# SupergunBasic.net
KiCad netlist of a schematic drawn in EAGLE
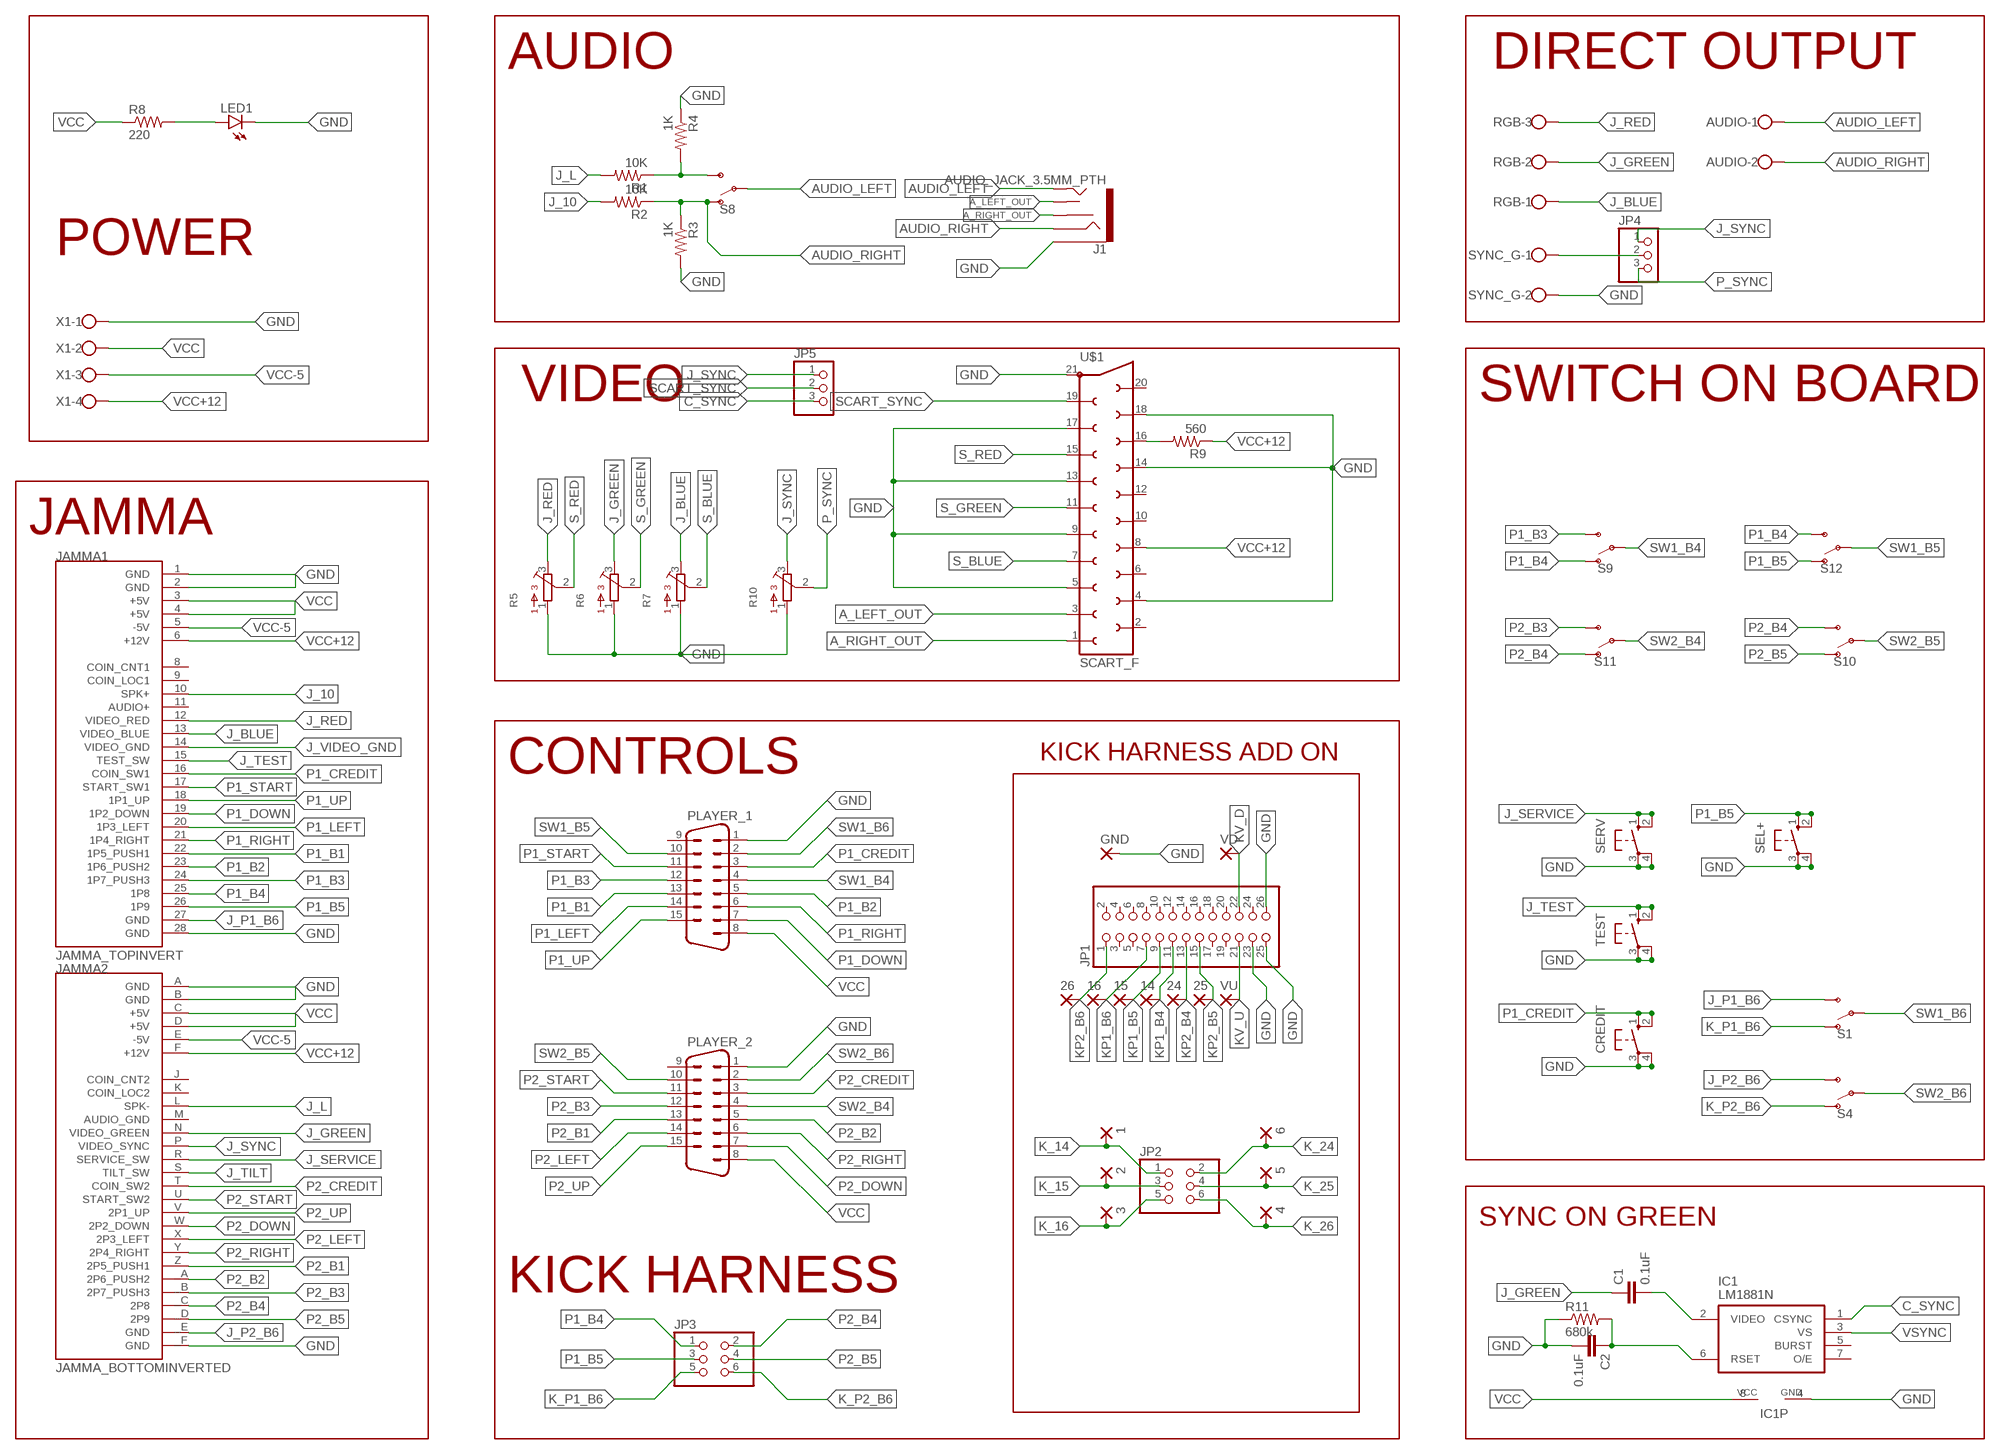
[diagram p0: schematic, sheet 1]

(export (version "E")
  (design (tool "Eeschema 10.0.6"))
  (components
    (comp (ref "1")
      (value "SMD2")
      (footprint "eagle-import:SMD1,27-2,54")
      (libsource (lib "eagle-import") (part "SMD2"))
    )
    (comp (ref "2")
      (value "SMD2")
      (footprint "eagle-import:SMD1,27-2,54")
      (libsource (lib "eagle-import") (part "SMD2"))
    )
    (comp (ref "3")
      (value "SMD2")
      (footprint "eagle-import:SMD1,27-2,54")
      (libsource (lib "eagle-import") (part "SMD2"))
    )
    (comp (ref "4")
      (value "SMD2")
      (footprint "eagle-import:SMD1,27-2,54")
      (libsource (lib "eagle-import") (part "SMD2"))
    )
    (comp (ref "5")
      (value "SMD2")
      (footprint "eagle-import:SMD1,27-2,54")
      (libsource (lib "eagle-import") (part "SMD2"))
    )
    (comp (ref "6")
      (value "SMD2")
      (footprint "eagle-import:SMD1,27-2,54")
      (libsource (lib "eagle-import") (part "SMD2"))
    )
    (comp (ref "14")
      (value "SMD2")
      (footprint "eagle-import:SMD1,27-2,54")
      (libsource (lib "eagle-import") (part "SMD2"))
    )
    (comp (ref "15")
      (value "SMD2")
      (footprint "eagle-import:SMD1,27-2,54")
      (libsource (lib "eagle-import") (part "SMD2"))
    )
    (comp (ref "16")
      (value "SMD2")
      (footprint "eagle-import:SMD1,27-2,54")
      (libsource (lib "eagle-import") (part "SMD2"))
    )
    (comp (ref "24")
      (value "SMD2")
      (footprint "eagle-import:SMD1,27-2,54")
      (libsource (lib "eagle-import") (part "SMD2"))
    )
    (comp (ref "25")
      (value "SMD2")
      (footprint "eagle-import:SMD1,27-2,54")
      (libsource (lib "eagle-import") (part "SMD2"))
    )
    (comp (ref "26")
      (value "SMD2")
      (footprint "eagle-import:SMD1,27-2,54")
      (libsource (lib "eagle-import") (part "SMD2"))
    )
    (comp (ref "AUDIO")
      (value "W237-102")
      (footprint "eagle-import:W237-102")
      (fields (field (name "MPN") "237-102"))
      (libsource (lib "eagle-import") (part "W237-102"))
    )
    (comp (ref "C1")
      (value "0.1uF")
      (footprint "eagle-import:CAP-PTH-SMALL-KIT")
      (libsource (lib "eagle-import") (part "0.1UF-KIT-EZ-50V-20%"))
    )
    (comp (ref "C2")
      (value "0.1uF")
      (footprint "eagle-import:CAP-PTH-SMALL-KIT")
      (libsource (lib "eagle-import") (part "0.1UF-KIT-EZ-50V-20%"))
    )
    (comp (ref "CREDIT")
      (value "10-XX")
      (footprint "eagle-import:B3F-10XX")
      (fields (field (name "MPN") "B3F-1000"))
      (libsource (lib "eagle-import") (part "10-XX"))
    )
    (comp (ref "GND")
      (value "SMD2")
      (footprint "eagle-import:SMD1,27-2,54")
      (libsource (lib "eagle-import") (part "SMD2"))
    )
    (comp (ref "IC1")
      (value "LM1881N")
      (footprint "eagle-import:DIL08")
      (libsource (lib "eagle-import") (part "LM1881N"))
    )
    (comp (ref "J1")
      (value "AUDIO_JACK_3.5MM_PTH")
      (footprint "eagle-import:AUDIO-JACK")
      (libsource (lib "eagle-import") (part "AUDIO_JACK_3.5MM_PTH"))
    )
    (comp (ref "JAMMA1")
      (value "JAMMA_TOPINVERT")
      (footprint "eagle-import:JAMMA_TOP_INV")
      (libsource (lib "eagle-import") (part "JAMMA_TOPINVERT"))
    )
    (comp (ref "JAMMA2")
      (value "JAMMA_BOTTOMINVERTED")
      (footprint "eagle-import:JAMMA_BOTTOM_INV")
      (libsource (lib "eagle-import") (part "JAMMA_BOTTOMINVERTED"))
    )
    (comp (ref "JP1")
      (value "PINHD-2X13")
      (footprint "eagle-import:2X13")
      (libsource (lib "eagle-import") (part "PINHD-2X13"))
    )
    (comp (ref "JP2")
      (value "PINHD-2X3")
      (footprint "eagle-import:2X03")
      (libsource (lib "eagle-import") (part "PINHD-2X3"))
    )
    (comp (ref "JP3")
      (value "PINHD-2X3")
      (footprint "eagle-import:2X03")
      (libsource (lib "eagle-import") (part "PINHD-2X3"))
    )
    (comp (ref "JP4")
      (value "PINHD-1X3")
      (footprint "eagle-import:1X03")
      (libsource (lib "eagle-import") (part "PINHD-1X3"))
    )
    (comp (ref "JP5")
      (value "PINHD-1X3")
      (footprint "eagle-import:1X03")
      (libsource (lib "eagle-import") (part "PINHD-1X3"))
    )
    (comp (ref "LED1")
      (value "LEDLD260")
      (footprint "eagle-import:LD260")
      (libsource (lib "eagle-import") (part "LEDLD260"))
    )
    (comp (ref "PLAYER_1")
      (value "M15HP")
      (footprint "eagle-import:M15HP")
      (libsource (lib "eagle-import") (part "M15HP"))
    )
    (comp (ref "PLAYER_2")
      (value "M15HP")
      (footprint "eagle-import:M15HP")
      (libsource (lib "eagle-import") (part "M15HP"))
    )
    (comp (ref "R1")
      (value "10K")
      (footprint "eagle-import:0204_7")
      (libsource (lib "eagle-import") (part "R-US_0204/7"))
    )
    (comp (ref "R2")
      (value "10K")
      (footprint "eagle-import:0204_7")
      (libsource (lib "eagle-import") (part "R-US_0204/7"))
    )
    (comp (ref "R3")
      (value "1K")
      (footprint "eagle-import:0204_7")
      (libsource (lib "eagle-import") (part "R-US_0204/7"))
    )
    (comp (ref "R4")
      (value "1K")
      (footprint "eagle-import:0204_7")
      (libsource (lib "eagle-import") (part "R-US_0204/7"))
    )
    (comp (ref "R5")
      (value "3362P")
      (footprint "eagle-import:3362P")
      (libsource (lib "eagle-import") (part "3362P"))
    )
    (comp (ref "R6")
      (value "3362P")
      (footprint "eagle-import:3362P")
      (libsource (lib "eagle-import") (part "3362P"))
    )
    (comp (ref "R7")
      (value "3362P")
      (footprint "eagle-import:3362P")
      (libsource (lib "eagle-import") (part "3362P"))
    )
    (comp (ref "R8")
      (value "220")
      (footprint "eagle-import:0204_7")
      (libsource (lib "eagle-import") (part "R-US_0204/7"))
    )
    (comp (ref "R9")
      (value "560")
      (footprint "eagle-import:0204_7")
      (libsource (lib "eagle-import") (part "R-US_0204/7"))
    )
    (comp (ref "R10")
      (value "3362P")
      (footprint "eagle-import:3362P")
      (libsource (lib "eagle-import") (part "3362P"))
    )
    (comp (ref "R11")
      (value "680k")
      (footprint "eagle-import:0204_7")
      (libsource (lib "eagle-import") (part "R-US_0204/7"))
    )
    (comp (ref "RGB")
      (value "W237-103")
      (footprint "eagle-import:W237-103")
      (fields (field (name "MPN") "237-103"))
      (libsource (lib "eagle-import") (part "W237-103"))
    )
    (comp (ref "S1")
      (value "SWITCH-SPDT-PTH-11.6X4.0MM")
      (footprint "eagle-import:SWITCH_SPDT_PTH_11.6X4.0MM")
      (libsource (lib "eagle-import") (part "SWITCH-SPDT-PTH-11.6X4.0MM"))
    )
    (comp (ref "S4")
      (value "SWITCH-SPDT-PTH-11.6X4.0MM")
      (footprint "eagle-import:SWITCH_SPDT_PTH_11.6X4.0MM")
      (libsource (lib "eagle-import") (part "SWITCH-SPDT-PTH-11.6X4.0MM"))
    )
    (comp (ref "S8")
      (value "SWITCH-SPDT-PTH-11.6X4.0MM")
      (footprint "eagle-import:SWITCH_SPDT_PTH_11.6X4.0MM")
      (libsource (lib "eagle-import") (part "SWITCH-SPDT-PTH-11.6X4.0MM"))
    )
    (comp (ref "S9")
      (value "SWITCH-SPDT-PTH-11.6X4.0MM")
      (footprint "eagle-import:SWITCH_SPDT_PTH_11.6X4.0MM")
      (libsource (lib "eagle-import") (part "SWITCH-SPDT-PTH-11.6X4.0MM"))
    )
    (comp (ref "S10")
      (value "SWITCH-SPDT-PTH-11.6X4.0MM")
      (footprint "eagle-import:SWITCH_SPDT_PTH_11.6X4.0MM")
      (libsource (lib "eagle-import") (part "SWITCH-SPDT-PTH-11.6X4.0MM"))
    )
    (comp (ref "S11")
      (value "SWITCH-SPDT-PTH-11.6X4.0MM")
      (footprint "eagle-import:SWITCH_SPDT_PTH_11.6X4.0MM")
      (libsource (lib "eagle-import") (part "SWITCH-SPDT-PTH-11.6X4.0MM"))
    )
    (comp (ref "S12")
      (value "SWITCH-SPDT-PTH-11.6X4.0MM")
      (footprint "eagle-import:SWITCH_SPDT_PTH_11.6X4.0MM")
      (libsource (lib "eagle-import") (part "SWITCH-SPDT-PTH-11.6X4.0MM"))
    )
    (comp (ref "SEL+")
      (value "10-XX")
      (footprint "eagle-import:B3F-10XX")
      (fields (field (name "MPN") "B3F-1000"))
      (libsource (lib "eagle-import") (part "10-XX"))
    )
    (comp (ref "SERV")
      (value "10-XX")
      (footprint "eagle-import:B3F-10XX")
      (fields (field (name "MPN") "B3F-1000"))
      (libsource (lib "eagle-import") (part "10-XX"))
    )
    (comp (ref "SYNC_G")
      (value "W237-102")
      (footprint "eagle-import:W237-102")
      (fields (field (name "MPN") "237-102"))
      (libsource (lib "eagle-import") (part "W237-102"))
    )
    (comp (ref "TEST")
      (value "10-XX")
      (footprint "eagle-import:B3F-10XX")
      (fields (field (name "MPN") "B3F-1000"))
      (libsource (lib "eagle-import") (part "10-XX"))
    )
    (comp (ref "U$1")
      (value "SCART_F")
      (footprint "eagle-import:SCART_F")
      (libsource (lib "eagle-import") (part "SCART_F"))
    )
    (comp (ref "VD")
      (value "SMD2")
      (footprint "eagle-import:SMD1,27-2,54")
      (libsource (lib "eagle-import") (part "SMD2"))
    )
    (comp (ref "VU")
      (value "SMD2")
      (footprint "eagle-import:SMD1,27-2,54")
      (libsource (lib "eagle-import") (part "SMD2"))
    )
    (comp (ref "X1")
      (value "W237-4")
      (footprint "eagle-import:W237-4")
      (libsource (lib "eagle-import") (part "W237-4"))
    )
  )
  (nets
    (net (code "1") (name "AUDIO_LEFT") (class "Default")
      (node (ref "AUDIO") (pin "1") (pinfunction "KL_1") (pintype "passive"))
      (node (ref "J1") (pin "TIP") (pinfunction "TIP_TIP") (pintype "bidirectional"))
      (node (ref "S8") (pin "2") (pinfunction "P_2") (pintype "passive"))
    )
    (net (code "2") (name "AUDIO_RIGHT") (class "Default")
      (node (ref "AUDIO") (pin "2") (pinfunction "KL_2") (pintype "passive"))
      (node (ref "J1") (pin "RING") (pinfunction "RING_RING") (pintype "bidirectional"))
      (node (ref "R2") (pin "1") (pinfunction "1_1") (pintype "passive"))
      (node (ref "R3") (pin "1") (pinfunction "1_1") (pintype "passive"))
      (node (ref "S8") (pin "1") (pinfunction "O_1") (pintype "passive"))
    )
    (net (code "3") (name "A_LEFT_OUT") (class "Default")
      (node (ref "J1") (pin "TSH") (pinfunction "TSH_TSH") (pintype "bidirectional"))
      (node (ref "U$1") (pin "3") (pinfunction "3_3") (pintype "passive"))
    )
    (net (code "4") (name "A_RIGHT_OUT") (class "Default")
      (node (ref "J1") (pin "RSH") (pinfunction "RSH_RSH") (pintype "bidirectional"))
      (node (ref "U$1") (pin "1") (pinfunction "1_1") (pintype "passive"))
    )
    (net (code "5") (name "C_SYNC") (class "Default")
      (node (ref "IC1") (pin "1") (pinfunction "CSYNC_1") (pintype "output"))
      (node (ref "JP5") (pin "3") (pinfunction "3_3") (pintype "passive"))
    )
    (net (code "6") (name "GND") (class "Default")
      (node (ref "C2") (pin "2") (pinfunction "2_2") (pintype "passive"))
      (node (ref "CREDIT") (pin "3") (pinfunction "P_3") (pintype "passive"))
      (node (ref "CREDIT") (pin "4") (pinfunction "P1_4") (pintype "passive"))
      (node (ref "GND") (pin "1") (pinfunction "P_1") (pintype "passive"))
      (node (ref "IC1") (pin "4") (pinfunction "GND_4") (pintype "power_in"))
      (node (ref "J1") (pin "SLEEVE") (pinfunction "SLEEVE_SLEEVE") (pintype "bidirectional"))
      (node (ref "JAMMA1") (pin "1") (pinfunction "GND_1") (pintype "power_in"))
      (node (ref "JAMMA1") (pin "2") (pinfunction "GND_2") (pintype "power_in"))
      (node (ref "JAMMA1") (pin "28") (pinfunction "GND_28") (pintype "power_in"))
      (node (ref "JAMMA2") (pin "A") (pinfunction "GND_A") (pintype "power_in"))
      (node (ref "JAMMA2") (pin "B") (pinfunction "GND_B") (pintype "power_in"))
      (node (ref "JAMMA2") (pin "_F") (pinfunction "GND__F") (pintype "power_in"))
      (node (ref "JP1") (pin "23") (pinfunction "23_23") (pintype "passive"))
      (node (ref "JP1") (pin "25") (pinfunction "25_25") (pintype "passive"))
      (node (ref "JP1") (pin "26") (pinfunction "26_26") (pintype "passive"))
      (node (ref "LED1") (pin "K") (pinfunction "C_K") (pintype "passive"))
      (node (ref "PLAYER_1") (pin "1") (pinfunction "1_1") (pintype "passive"))
      (node (ref "PLAYER_2") (pin "1") (pinfunction "1_1") (pintype "passive"))
      (node (ref "R10") (pin "1") (pinfunction "1_1") (pintype "passive"))
      (node (ref "R11") (pin "1") (pinfunction "1_1") (pintype "passive"))
      (node (ref "R3") (pin "2") (pinfunction "2_2") (pintype "passive"))
      (node (ref "R4") (pin "1") (pinfunction "1_1") (pintype "passive"))
      (node (ref "R5") (pin "1") (pinfunction "1_1") (pintype "passive"))
      (node (ref "R6") (pin "1") (pinfunction "1_1") (pintype "passive"))
      (node (ref "R7") (pin "1") (pinfunction "1_1") (pintype "passive"))
      (node (ref "SEL+") (pin "3") (pinfunction "P_3") (pintype "passive"))
      (node (ref "SEL+") (pin "4") (pinfunction "P1_4") (pintype "passive"))
      (node (ref "SERV") (pin "3") (pinfunction "P_3") (pintype "passive"))
      (node (ref "SERV") (pin "4") (pinfunction "P1_4") (pintype "passive"))
      (node (ref "SYNC_G") (pin "2") (pinfunction "KL_2") (pintype "passive"))
      (node (ref "TEST") (pin "3") (pinfunction "P_3") (pintype "passive"))
      (node (ref "TEST") (pin "4") (pinfunction "P1_4") (pintype "passive"))
      (node (ref "U$1") (pin "13") (pinfunction "13_13") (pintype "passive"))
      (node (ref "U$1") (pin "14") (pinfunction "14_14") (pintype "passive"))
      (node (ref "U$1") (pin "17") (pinfunction "17_17") (pintype "passive"))
      (node (ref "U$1") (pin "18") (pinfunction "18_18") (pintype "passive"))
      (node (ref "U$1") (pin "21") (pinfunction "21_21") (pintype "passive"))
      (node (ref "U$1") (pin "4") (pinfunction "4_4") (pintype "passive"))
      (node (ref "U$1") (pin "5") (pinfunction "5_5") (pintype "passive"))
      (node (ref "U$1") (pin "9") (pinfunction "9_9") (pintype "passive"))
      (node (ref "X1") (pin "1") (pinfunction "KL_1") (pintype "passive"))
    )
    (net (code "7") (name "J_10") (class "Default")
      (node (ref "JAMMA1") (pin "10") (pinfunction "SPK+_10") (pintype "output"))
      (node (ref "R2") (pin "2") (pinfunction "2_2") (pintype "passive"))
    )
    (net (code "8") (name "J_BLUE") (class "Default")
      (node (ref "JAMMA1") (pin "13") (pinfunction "VIDEO_BLUE_13") (pintype "output"))
      (node (ref "R7") (pin "3") (pinfunction "3_3") (pintype "passive"))
      (node (ref "RGB") (pin "1") (pinfunction "KL_1") (pintype "passive"))
    )
    (net (code "9") (name "J_GREEN") (class "Default")
      (node (ref "C1") (pin "1") (pinfunction "1_1") (pintype "passive"))
      (node (ref "JAMMA2") (pin "N") (pinfunction "VIDEO_GREEN_N") (pintype "output"))
      (node (ref "R6") (pin "3") (pinfunction "3_3") (pintype "passive"))
      (node (ref "RGB") (pin "2") (pinfunction "KL_2") (pintype "passive"))
    )
    (net (code "10") (name "J_L") (class "Default")
      (node (ref "JAMMA2") (pin "L") (pinfunction "SPK-_L") (pintype "output"))
      (node (ref "R1") (pin "2") (pinfunction "2_2") (pintype "passive"))
    )
    (net (code "11") (name "J_P1_B6") (class "Default")
      (node (ref "JAMMA1") (pin "27") (pinfunction "GND_27") (pintype "power_in"))
      (node (ref "S1") (pin "3") (pinfunction "S_3") (pintype "passive"))
    )
    (net (code "12") (name "J_P2_B6") (class "Default")
      (node (ref "JAMMA2") (pin "_E") (pinfunction "GND__E") (pintype "power_in"))
      (node (ref "S4") (pin "3") (pinfunction "S_3") (pintype "passive"))
    )
    (net (code "13") (name "J_RED") (class "Default")
      (node (ref "JAMMA1") (pin "12") (pinfunction "VIDEO_RED_12") (pintype "output"))
      (node (ref "R5") (pin "3") (pinfunction "3_3") (pintype "passive"))
      (node (ref "RGB") (pin "3") (pinfunction "KL_3") (pintype "passive"))
    )
    (net (code "14") (name "J_SERVICE") (class "Default")
      (node (ref "JAMMA2") (pin "R") (pinfunction "SERVICE_SW_R") (pintype "input"))
      (node (ref "SERV") (pin "1") (pinfunction "S_1") (pintype "passive"))
      (node (ref "SERV") (pin "2") (pinfunction "S1_2") (pintype "passive"))
    )
    (net (code "15") (name "J_SYNC") (class "Default")
      (node (ref "JAMMA2") (pin "P") (pinfunction "VIDEO_SYNC_P") (pintype "output"))
      (node (ref "JP4") (pin "1") (pinfunction "1_1") (pintype "passive"))
      (node (ref "JP5") (pin "1") (pinfunction "1_1") (pintype "passive"))
      (node (ref "R10") (pin "3") (pinfunction "3_3") (pintype "passive"))
    )
    (net (code "16") (name "J_TEST") (class "Default")
      (node (ref "JAMMA1") (pin "15") (pinfunction "TEST_SW_15") (pintype "input"))
      (node (ref "TEST") (pin "1") (pinfunction "S_1") (pintype "passive"))
      (node (ref "TEST") (pin "2") (pinfunction "S1_2") (pintype "passive"))
    )
    (net (code "17") (name "J_TILT") (class "Default")
      (node (ref "JAMMA2") (pin "S") (pinfunction "TILT_SW_S") (pintype "input"))
    )
    (net (code "18") (name "J_VIDEO_GND") (class "Default")
      (node (ref "JAMMA1") (pin "14") (pinfunction "VIDEO_GND_14") (pintype "output"))
    )
    (net (code "19") (name "KP1_B4") (class "Default")
      (node (ref "14") (pin "1") (pinfunction "P_1") (pintype "passive"))
      (node (ref "JP1") (pin "11") (pinfunction "11_11") (pintype "passive"))
    )
    (net (code "20") (name "KP1_B5") (class "Default")
      (node (ref "15") (pin "1") (pinfunction "P_1") (pintype "passive"))
      (node (ref "JP1") (pin "9") (pinfunction "9_9") (pintype "passive"))
    )
    (net (code "21") (name "KP1_B6") (class "Default")
      (node (ref "16") (pin "1") (pinfunction "P_1") (pintype "passive"))
      (node (ref "JP1") (pin "7") (pinfunction "7_7") (pintype "passive"))
    )
    (net (code "22") (name "KP2_B4") (class "Default")
      (node (ref "24") (pin "1") (pinfunction "P_1") (pintype "passive"))
      (node (ref "JP1") (pin "13") (pinfunction "13_13") (pintype "passive"))
    )
    (net (code "23") (name "KP2_B5") (class "Default")
      (node (ref "25") (pin "1") (pinfunction "P_1") (pintype "passive"))
      (node (ref "JP1") (pin "15") (pinfunction "15_15") (pintype "passive"))
    )
    (net (code "24") (name "KP2_B6") (class "Default")
      (node (ref "26") (pin "1") (pinfunction "P_1") (pintype "passive"))
      (node (ref "JP1") (pin "1") (pinfunction "1_1") (pintype "passive"))
    )
    (net (code "25") (name "KV_D") (class "Default")
      (node (ref "JP1") (pin "22") (pinfunction "22_22") (pintype "passive"))
      (node (ref "VD") (pin "1") (pinfunction "P_1") (pintype "passive"))
    )
    (net (code "26") (name "KV_U") (class "Default")
      (node (ref "JP1") (pin "21") (pinfunction "21_21") (pintype "passive"))
      (node (ref "VU") (pin "1") (pinfunction "P_1") (pintype "passive"))
    )
    (net (code "27") (name "K_14") (class "Default")
      (node (ref "1") (pin "1") (pinfunction "P_1") (pintype "passive"))
      (node (ref "JP2") (pin "1") (pinfunction "1_1") (pintype "passive"))
    )
    (net (code "28") (name "K_15") (class "Default")
      (node (ref "2") (pin "1") (pinfunction "P_1") (pintype "passive"))
      (node (ref "JP2") (pin "3") (pinfunction "3_3") (pintype "passive"))
    )
    (net (code "29") (name "K_16") (class "Default")
      (node (ref "3") (pin "1") (pinfunction "P_1") (pintype "passive"))
      (node (ref "JP2") (pin "5") (pinfunction "5_5") (pintype "passive"))
    )
    (net (code "30") (name "K_24") (class "Default")
      (node (ref "6") (pin "1") (pinfunction "P_1") (pintype "passive"))
      (node (ref "JP2") (pin "2") (pinfunction "2_2") (pintype "passive"))
    )
    (net (code "31") (name "K_25") (class "Default")
      (node (ref "5") (pin "1") (pinfunction "P_1") (pintype "passive"))
      (node (ref "JP2") (pin "4") (pinfunction "4_4") (pintype "passive"))
    )
    (net (code "32") (name "K_26") (class "Default")
      (node (ref "4") (pin "1") (pinfunction "P_1") (pintype "passive"))
      (node (ref "JP2") (pin "6") (pinfunction "6_6") (pintype "passive"))
    )
    (net (code "33") (name "K_P1_B6") (class "Default")
      (node (ref "JP3") (pin "5") (pinfunction "5_5") (pintype "passive"))
      (node (ref "S1") (pin "1") (pinfunction "O_1") (pintype "passive"))
    )
    (net (code "34") (name "K_P2_B6") (class "Default")
      (node (ref "JP3") (pin "6") (pinfunction "6_6") (pintype "passive"))
      (node (ref "S4") (pin "1") (pinfunction "O_1") (pintype "passive"))
    )
    (net (code "35") (name "Net-(IC1A-RSET)") (class "Default")
      (node (ref "C2") (pin "1") (pinfunction "1_1") (pintype "passive"))
      (node (ref "IC1") (pin "6") (pinfunction "RSET_6") (pintype "passive"))
      (node (ref "R11") (pin "2") (pinfunction "2_2") (pintype "passive"))
    )
    (net (code "36") (name "Net-(IC1A-VIDEO)") (class "Default")
      (node (ref "C1") (pin "2") (pinfunction "2_2") (pintype "passive"))
      (node (ref "IC1") (pin "2") (pinfunction "VIDEO_2") (pintype "input"))
    )
    (net (code "37") (name "Net-(LED1-PadA)") (class "Default")
      (node (ref "LED1") (pin "A") (pinfunction "A_A") (pintype "passive"))
      (node (ref "R8") (pin "2") (pinfunction "2_2") (pintype "passive"))
    )
    (net (code "38") (name "Net-(R9-Pad2)") (class "Default")
      (node (ref "R9") (pin "2") (pinfunction "2_2") (pintype "passive"))
      (node (ref "U$1") (pin "16") (pinfunction "16_16") (pintype "passive"))
    )
    (net (code "39") (name "Net-(S8-S)") (class "Default")
      (node (ref "R1") (pin "1") (pinfunction "1_1") (pintype "passive"))
      (node (ref "R4") (pin "2") (pinfunction "2_2") (pintype "passive"))
      (node (ref "S8") (pin "3") (pinfunction "S_3") (pintype "passive"))
    )
    (net (code "40") (name "Net-(SYNC_GA-KL)") (class "Default")
      (node (ref "JP4") (pin "2") (pinfunction "2_2") (pintype "passive"))
      (node (ref "SYNC_G") (pin "1") (pinfunction "KL_1") (pintype "passive"))
    )
    (net (code "41") (name "P1_B1") (class "Default")
      (node (ref "JAMMA1") (pin "22") (pinfunction "1P5_PUSH1_22") (pintype "input"))
      (node (ref "PLAYER_1") (pin "13") (pinfunction "13_13") (pintype "passive"))
    )
    (net (code "42") (name "P1_B2") (class "Default")
      (node (ref "JAMMA1") (pin "23") (pinfunction "1P6_PUSH2_23") (pintype "input"))
      (node (ref "PLAYER_1") (pin "5") (pinfunction "5_5") (pintype "passive"))
    )
    (net (code "43") (name "P1_B3") (class "Default")
      (node (ref "JAMMA1") (pin "24") (pinfunction "1P7_PUSH3_24") (pintype "input"))
      (node (ref "PLAYER_1") (pin "12") (pinfunction "12_12") (pintype "passive"))
      (node (ref "S9") (pin "3") (pinfunction "S_3") (pintype "passive"))
    )
    (net (code "44") (name "P1_B4") (class "Default")
      (node (ref "JAMMA1") (pin "25") (pinfunction "1P8_25") (pintype "input"))
      (node (ref "JP3") (pin "1") (pinfunction "1_1") (pintype "passive"))
      (node (ref "S12") (pin "3") (pinfunction "S_3") (pintype "passive"))
      (node (ref "S9") (pin "1") (pinfunction "O_1") (pintype "passive"))
    )
    (net (code "45") (name "P1_B5") (class "Default")
      (node (ref "JAMMA1") (pin "26") (pinfunction "1P9_26") (pintype "input"))
      (node (ref "JP3") (pin "3") (pinfunction "3_3") (pintype "passive"))
      (node (ref "S12") (pin "1") (pinfunction "O_1") (pintype "passive"))
      (node (ref "SEL+") (pin "1") (pinfunction "S_1") (pintype "passive"))
      (node (ref "SEL+") (pin "2") (pinfunction "S1_2") (pintype "passive"))
    )
    (net (code "46") (name "P1_CREDIT") (class "Default")
      (node (ref "CREDIT") (pin "1") (pinfunction "S_1") (pintype "passive"))
      (node (ref "CREDIT") (pin "2") (pinfunction "S1_2") (pintype "passive"))
      (node (ref "JAMMA1") (pin "16") (pinfunction "COIN_SW1_16") (pintype "input"))
      (node (ref "PLAYER_1") (pin "3") (pinfunction "3_3") (pintype "passive"))
    )
    (net (code "47") (name "P1_DOWN") (class "Default")
      (node (ref "JAMMA1") (pin "19") (pinfunction "1P2_DOWN_19") (pintype "input"))
      (node (ref "PLAYER_1") (pin "7") (pinfunction "7_7") (pintype "passive"))
    )
    (net (code "48") (name "P1_LEFT") (class "Default")
      (node (ref "JAMMA1") (pin "20") (pinfunction "1P3_LEFT_20") (pintype "input"))
      (node (ref "PLAYER_1") (pin "14") (pinfunction "14_14") (pintype "passive"))
    )
    (net (code "49") (name "P1_RIGHT") (class "Default")
      (node (ref "JAMMA1") (pin "21") (pinfunction "1P4_RIGHT_21") (pintype "input"))
      (node (ref "PLAYER_1") (pin "6") (pinfunction "6_6") (pintype "passive"))
    )
    (net (code "50") (name "P1_START") (class "Default")
      (node (ref "JAMMA1") (pin "17") (pinfunction "START_SW1_17") (pintype "input"))
      (node (ref "PLAYER_1") (pin "11") (pinfunction "11_11") (pintype "passive"))
    )
    (net (code "51") (name "P1_UP") (class "Default")
      (node (ref "JAMMA1") (pin "18") (pinfunction "1P1_UP_18") (pintype "input"))
      (node (ref "PLAYER_1") (pin "15") (pinfunction "15_15") (pintype "passive"))
    )
    (net (code "52") (name "P2_B1") (class "Default")
      (node (ref "JAMMA2") (pin "Z") (pinfunction "2P5_PUSH1_Z") (pintype "input"))
      (node (ref "PLAYER_2") (pin "13") (pinfunction "13_13") (pintype "passive"))
    )
    (net (code "53") (name "P2_B2") (class "Default")
      (node (ref "JAMMA2") (pin "_A") (pinfunction "2P6_PUSH2__A") (pintype "input"))
      (node (ref "PLAYER_2") (pin "5") (pinfunction "5_5") (pintype "passive"))
    )
    (net (code "54") (name "P2_B3") (class "Default")
      (node (ref "JAMMA2") (pin "_B") (pinfunction "2P7_PUSH3__B") (pintype "input"))
      (node (ref "PLAYER_2") (pin "12") (pinfunction "12_12") (pintype "passive"))
      (node (ref "S11") (pin "3") (pinfunction "S_3") (pintype "passive"))
    )
    (net (code "55") (name "P2_B4") (class "Default")
      (node (ref "JAMMA2") (pin "_C") (pinfunction "2P8__C") (pintype "input"))
      (node (ref "JP3") (pin "2") (pinfunction "2_2") (pintype "passive"))
      (node (ref "S10") (pin "3") (pinfunction "S_3") (pintype "passive"))
      (node (ref "S11") (pin "1") (pinfunction "O_1") (pintype "passive"))
    )
    (net (code "56") (name "P2_B5") (class "Default")
      (node (ref "JAMMA2") (pin "_D") (pinfunction "2P9__D") (pintype "input"))
      (node (ref "JP3") (pin "4") (pinfunction "4_4") (pintype "passive"))
      (node (ref "S10") (pin "1") (pinfunction "O_1") (pintype "passive"))
    )
    (net (code "57") (name "P2_CREDIT") (class "Default")
      (node (ref "JAMMA2") (pin "T") (pinfunction "COIN_SW2_T") (pintype "input"))
      (node (ref "PLAYER_2") (pin "3") (pinfunction "3_3") (pintype "passive"))
    )
    (net (code "58") (name "P2_DOWN") (class "Default")
      (node (ref "JAMMA2") (pin "W") (pinfunction "2P2_DOWN_W") (pintype "input"))
      (node (ref "PLAYER_2") (pin "7") (pinfunction "7_7") (pintype "passive"))
    )
    (net (code "59") (name "P2_LEFT") (class "Default")
      (node (ref "JAMMA2") (pin "X") (pinfunction "2P3_LEFT_X") (pintype "input"))
      (node (ref "PLAYER_2") (pin "14") (pinfunction "14_14") (pintype "passive"))
    )
    (net (code "60") (name "P2_RIGHT") (class "Default")
      (node (ref "JAMMA2") (pin "Y") (pinfunction "2P4_RIGHT_Y") (pintype "input"))
      (node (ref "PLAYER_2") (pin "6") (pinfunction "6_6") (pintype "passive"))
    )
    (net (code "61") (name "P2_START") (class "Default")
      (node (ref "JAMMA2") (pin "U") (pinfunction "START_SW2_U") (pintype "input"))
      (node (ref "PLAYER_2") (pin "11") (pinfunction "11_11") (pintype "passive"))
    )
    (net (code "62") (name "P2_UP") (class "Default")
      (node (ref "JAMMA2") (pin "V") (pinfunction "2P1_UP_V") (pintype "input"))
      (node (ref "PLAYER_2") (pin "15") (pinfunction "15_15") (pintype "passive"))
    )
    (net (code "63") (name "P_SYNC") (class "Default")
      (node (ref "JP4") (pin "3") (pinfunction "3_3") (pintype "passive"))
      (node (ref "R10") (pin "2") (pinfunction "2_2") (pintype "passive"))
    )
    (net (code "64") (name "SCART_SYNC") (class "Default")
      (node (ref "JP5") (pin "2") (pinfunction "2_2") (pintype "passive"))
      (node (ref "U$1") (pin "19") (pinfunction "19_19") (pintype "passive"))
    )
    (net (code "65") (name "SW1_B4") (class "Default")
      (node (ref "PLAYER_1") (pin "4") (pinfunction "4_4") (pintype "passive"))
      (node (ref "S9") (pin "2") (pinfunction "P_2") (pintype "passive"))
    )
    (net (code "66") (name "SW1_B5") (class "Default")
      (node (ref "PLAYER_1") (pin "10") (pinfunction "10_10") (pintype "passive"))
      (node (ref "S12") (pin "2") (pinfunction "P_2") (pintype "passive"))
    )
    (net (code "67") (name "SW1_B6") (class "Default")
      (node (ref "PLAYER_1") (pin "2") (pinfunction "2_2") (pintype "passive"))
      (node (ref "S1") (pin "2") (pinfunction "P_2") (pintype "passive"))
    )
    (net (code "68") (name "SW2_B4") (class "Default")
      (node (ref "PLAYER_2") (pin "4") (pinfunction "4_4") (pintype "passive"))
      (node (ref "S11") (pin "2") (pinfunction "P_2") (pintype "passive"))
    )
    (net (code "69") (name "SW2_B5") (class "Default")
      (node (ref "PLAYER_2") (pin "10") (pinfunction "10_10") (pintype "passive"))
      (node (ref "S10") (pin "2") (pinfunction "P_2") (pintype "passive"))
    )
    (net (code "70") (name "SW2_B6") (class "Default")
      (node (ref "PLAYER_2") (pin "2") (pinfunction "2_2") (pintype "passive"))
      (node (ref "S4") (pin "2") (pinfunction "P_2") (pintype "passive"))
    )
    (net (code "71") (name "S_BLUE") (class "Default")
      (node (ref "R7") (pin "2") (pinfunction "2_2") (pintype "passive"))
      (node (ref "U$1") (pin "7") (pinfunction "7_7") (pintype "passive"))
    )
    (net (code "72") (name "S_GREEN") (class "Default")
      (node (ref "R6") (pin "2") (pinfunction "2_2") (pintype "passive"))
      (node (ref "U$1") (pin "11") (pinfunction "11_11") (pintype "passive"))
    )
    (net (code "73") (name "S_RED") (class "Default")
      (node (ref "R5") (pin "2") (pinfunction "2_2") (pintype "passive"))
      (node (ref "U$1") (pin "15") (pinfunction "15_15") (pintype "passive"))
    )
    (net (code "74") (name "VCC") (class "Default")
      (node (ref "IC1") (pin "8") (pinfunction "VCC_8") (pintype "power_in"))
      (node (ref "JAMMA1") (pin "3") (pinfunction "+5V_3") (pintype "power_in"))
      (node (ref "JAMMA1") (pin "4") (pinfunction "+5V_4") (pintype "power_in"))
      (node (ref "JAMMA2") (pin "C") (pinfunction "+5V_C") (pintype "power_in"))
      (node (ref "JAMMA2") (pin "D") (pinfunction "+5V_D") (pintype "power_in"))
      (node (ref "PLAYER_1") (pin "8") (pinfunction "8_8") (pintype "passive"))
      (node (ref "PLAYER_2") (pin "8") (pinfunction "8_8") (pintype "passive"))
      (node (ref "R8") (pin "1") (pinfunction "1_1") (pintype "passive"))
      (node (ref "X1") (pin "2") (pinfunction "KL_2") (pintype "passive"))
    )
    (net (code "75") (name "VCC+12") (class "Default")
      (node (ref "JAMMA1") (pin "6") (pinfunction "+12V_6") (pintype "power_in"))
      (node (ref "JAMMA2") (pin "F") (pinfunction "+12V_F") (pintype "power_in"))
      (node (ref "R9") (pin "1") (pinfunction "1_1") (pintype "passive"))
      (node (ref "U$1") (pin "8") (pinfunction "8_8") (pintype "passive"))
      (node (ref "X1") (pin "4") (pinfunction "KL_4") (pintype "passive"))
    )
    (net (code "76") (name "VCC-5") (class "Default")
      (node (ref "JAMMA1") (pin "5") (pinfunction "-5V_5") (pintype "power_in"))
      (node (ref "JAMMA2") (pin "E") (pinfunction "-5V_E") (pintype "power_in"))
      (node (ref "X1") (pin "3") (pinfunction "KL_3") (pintype "passive"))
    )
    (net (code "77") (name "VSYNC") (class "Default")
      (node (ref "IC1") (pin "3") (pinfunction "VS_3") (pintype "output"))
    )
    (net (code "78") (name "unconnected-(IC1A-BURST-Pad5)") (class "Default")
      (node (ref "IC1") (pin "5") (pinfunction "BURST_5") (pintype "output"))
    )
    (net (code "79") (name "unconnected-(IC1A-O{slash}E-Pad7)") (class "Default")
      (node (ref "IC1") (pin "7") (pinfunction "O/E_7") (pintype "output"))
    )
    (net (code "80") (name "unconnected-(JAMMA1-AUDIO+-Pad11)") (class "Default")
      (node (ref "JAMMA1") (pin "11") (pinfunction "AUDIO+_11") (pintype "output"))
    )
    (net (code "81") (name "unconnected-(JAMMA1-COIN_CNT1-Pad8)") (class "Default")
      (node (ref "JAMMA1") (pin "8") (pinfunction "COIN_CNT1_8") (pintype "output"))
    )
    (net (code "82") (name "unconnected-(JAMMA1-COIN_LOC1-Pad9)") (class "Default")
      (node (ref "JAMMA1") (pin "9") (pinfunction "COIN_LOC1_9") (pintype "output"))
    )
    (net (code "83") (name "unconnected-(JAMMA2-AUDIO_GND-PadM)") (class "Default")
      (node (ref "JAMMA2") (pin "M") (pinfunction "AUDIO_GND_M") (pintype "output"))
    )
    (net (code "84") (name "unconnected-(JAMMA2-COIN_CNT2-PadJ)") (class "Default")
      (node (ref "JAMMA2") (pin "J") (pinfunction "COIN_CNT2_J") (pintype "output"))
    )
    (net (code "85") (name "unconnected-(JAMMA2-COIN_LOC2-PadK)") (class "Default")
      (node (ref "JAMMA2") (pin "K") (pinfunction "COIN_LOC2_K") (pintype "output"))
    )
    (net (code "86") (name "unconnected-(JP1-Pad2)") (class "Default")
      (node (ref "JP1") (pin "2") (pinfunction "2_2") (pintype "passive"))
    )
    (net (code "87") (name "unconnected-(JP1-Pad3)") (class "Default")
      (node (ref "JP1") (pin "3") (pinfunction "3_3") (pintype "passive"))
    )
    (net (code "88") (name "unconnected-(JP1-Pad4)") (class "Default")
      (node (ref "JP1") (pin "4") (pinfunction "4_4") (pintype "passive"))
    )
    (net (code "89") (name "unconnected-(JP1-Pad5)") (class "Default")
      (node (ref "JP1") (pin "5") (pinfunction "5_5") (pintype "passive"))
    )
    (net (code "90") (name "unconnected-(JP1-Pad6)") (class "Default")
      (node (ref "JP1") (pin "6") (pinfunction "6_6") (pintype "passive"))
    )
    (net (code "91") (name "unconnected-(JP1-Pad8)") (class "Default")
      (node (ref "JP1") (pin "8") (pinfunction "8_8") (pintype "passive"))
    )
    (net (code "92") (name "unconnected-(JP1-Pad10)") (class "Default")
      (node (ref "JP1") (pin "10") (pinfunction "10_10") (pintype "passive"))
    )
    (net (code "93") (name "unconnected-(JP1-Pad12)") (class "Default")
      (node (ref "JP1") (pin "12") (pinfunction "12_12") (pintype "passive"))
    )
    (net (code "94") (name "unconnected-(JP1-Pad14)") (class "Default")
      (node (ref "JP1") (pin "14") (pinfunction "14_14") (pintype "passive"))
    )
    (net (code "95") (name "unconnected-(JP1-Pad16)") (class "Default")
      (node (ref "JP1") (pin "16") (pinfunction "16_16") (pintype "passive"))
    )
    (net (code "96") (name "unconnected-(JP1-Pad17)") (class "Default")
      (node (ref "JP1") (pin "17") (pinfunction "17_17") (pintype "passive"))
    )
    (net (code "97") (name "unconnected-(JP1-Pad18)") (class "Default")
      (node (ref "JP1") (pin "18") (pinfunction "18_18") (pintype "passive"))
    )
    (net (code "98") (name "unconnected-(JP1-Pad19)") (class "Default")
      (node (ref "JP1") (pin "19") (pinfunction "19_19") (pintype "passive"))
    )
    (net (code "99") (name "unconnected-(JP1-Pad20)") (class "Default")
      (node (ref "JP1") (pin "20") (pinfunction "20_20") (pintype "passive"))
    )
    (net (code "100") (name "unconnected-(JP1-Pad24)") (class "Default")
      (node (ref "JP1") (pin "24") (pinfunction "24_24") (pintype "passive"))
    )
    (net (code "101") (name "unconnected-(PLAYER_1-Pad9)") (class "Default")
      (node (ref "PLAYER_1") (pin "9") (pinfunction "9_9") (pintype "passive"))
    )
    (net (code "102") (name "unconnected-(PLAYER_2-Pad9)") (class "Default")
      (node (ref "PLAYER_2") (pin "9") (pinfunction "9_9") (pintype "passive"))
    )
    (net (code "103") (name "unconnected-(U$1-Pad2)") (class "Default")
      (node (ref "U$1") (pin "2") (pinfunction "2_2") (pintype "passive"))
    )
    (net (code "104") (name "unconnected-(U$1-Pad6)") (class "Default")
      (node (ref "U$1") (pin "6") (pinfunction "6_6") (pintype "passive"))
    )
    (net (code "105") (name "unconnected-(U$1-Pad10)") (class "Default")
      (node (ref "U$1") (pin "10") (pinfunction "10_10") (pintype "passive"))
    )
    (net (code "106") (name "unconnected-(U$1-Pad12)") (class "Default")
      (node (ref "U$1") (pin "12") (pinfunction "12_12") (pintype "passive"))
    )
    (net (code "107") (name "unconnected-(U$1-Pad20)") (class "Default")
      (node (ref "U$1") (pin "20") (pinfunction "20_20") (pintype "passive"))
    )
  )
)
